# TriStateBuffer2.net
KiCad netlist of a schematic drawn in EAGLE
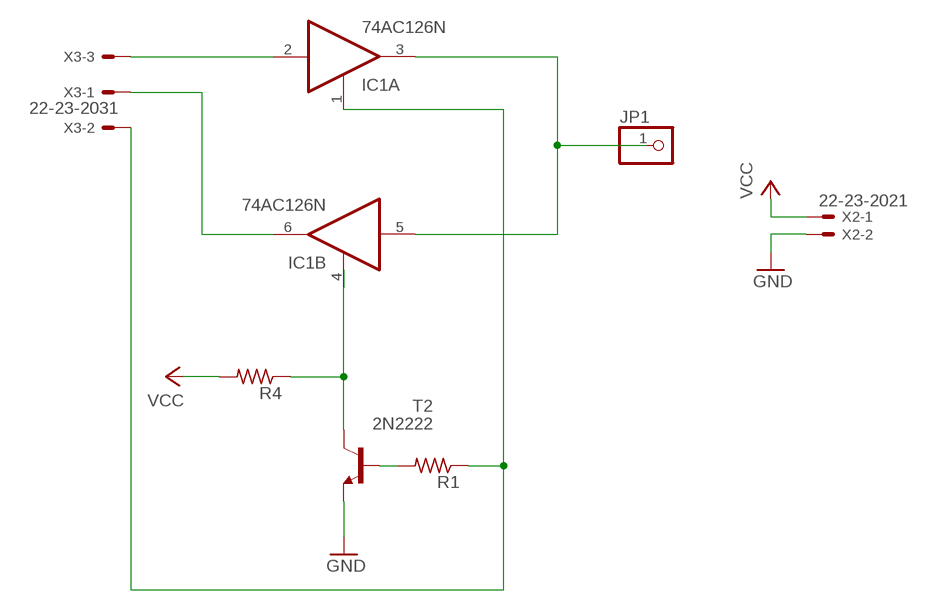
[diagram p0: schematic, sheet 1]

(export (version "E")
  (design (tool "Eeschema 10.0.6"))
  (components
    (comp (ref "IC1")
      (value "74AC126N")
      (footprint "eagle-import:DIL14")
      (libsource (lib "eagle-import") (part "74126NAC"))
    )
    (comp (ref "JP1")
      (value "PINHD-1X1")
      (footprint "eagle-import:1X01")
      (libsource (lib "eagle-import") (part "PINHD-1X1"))
    )
    (comp (ref "R1")
      (value "R-US_0309/12")
      (footprint "eagle-import:0309_12")
      (libsource (lib "eagle-import") (part "R-US_0309/12"))
    )
    (comp (ref "R4")
      (value "R-US_0309/12")
      (footprint "eagle-import:0309_12")
      (libsource (lib "eagle-import") (part "R-US_0309/12"))
    )
    (comp (ref "T2")
      (value "2N2222")
      (footprint "eagle-import:TO92-EBC-OVAL")
      (libsource (lib "eagle-import") (part "2N2222"))
    )
    (comp (ref "X2")
      (value "22-23-2021")
      (footprint "eagle-import:22-23-2021")
      (fields (field (name "MF") "MOLEX"))
      (libsource (lib "eagle-import") (part "22-23-2021"))
    )
    (comp (ref "X3")
      (value "22-23-2031")
      (footprint "eagle-import:22-23-2031")
      (fields (field (name "MF") "MOLEX"))
      (libsource (lib "eagle-import") (part "22-23-2031"))
    )
  )
  (nets
    (net (code "1") (name "GND") (class "Default")
      (node (ref "T2") (pin "E") (pinfunction "E_E") (pintype "passive"))
      (node (ref "X2") (pin "2") (pinfunction "S_2") (pintype "passive"))
    )
    (net (code "2") (name "Net-(IC1A-I)") (class "Default")
      (node (ref "IC1") (pin "2") (pinfunction "I_2") (pintype "input"))
      (node (ref "X3") (pin "3") (pinfunction "S_3") (pintype "passive"))
    )
    (net (code "3") (name "Net-(IC1A-O)") (class "Default")
      (node (ref "IC1") (pin "3") (pinfunction "O_3") (pintype "output"))
      (node (ref "IC1") (pin "5") (pinfunction "I_5") (pintype "input"))
      (node (ref "JP1") (pin "1") (pinfunction "1_1") (pintype "passive"))
    )
    (net (code "4") (name "Net-(IC1A-OE)") (class "Default")
      (node (ref "IC1") (pin "1") (pinfunction "OE_1") (pintype "input"))
      (node (ref "R1") (pin "1") (pinfunction "1_1") (pintype "passive"))
      (node (ref "X3") (pin "2") (pinfunction "S_2") (pintype "passive"))
    )
    (net (code "5") (name "Net-(IC1B-O)") (class "Default")
      (node (ref "IC1") (pin "6") (pinfunction "O_6") (pintype "output"))
      (node (ref "X3") (pin "1") (pinfunction "S_1") (pintype "passive"))
    )
    (net (code "6") (name "Net-(IC1B-OE)") (class "Default")
      (node (ref "IC1") (pin "4") (pinfunction "OE_4") (pintype "input"))
      (node (ref "R4") (pin "1") (pinfunction "1_1") (pintype "passive"))
      (node (ref "T2") (pin "C") (pinfunction "C_C") (pintype "passive"))
    )
    (net (code "7") (name "Net-(R1-Pad2)") (class "Default")
      (node (ref "R1") (pin "2") (pinfunction "2_2") (pintype "passive"))
      (node (ref "T2") (pin "B") (pinfunction "B_B") (pintype "passive"))
    )
    (net (code "8") (name "VCC") (class "Default")
      (node (ref "R4") (pin "2") (pinfunction "2_2") (pintype "passive"))
      (node (ref "X2") (pin "1") (pinfunction "S_1") (pintype "passive"))
    )
  )
)
